# Converter.net
KiCad netlist of a schematic drawn in Altium Designer
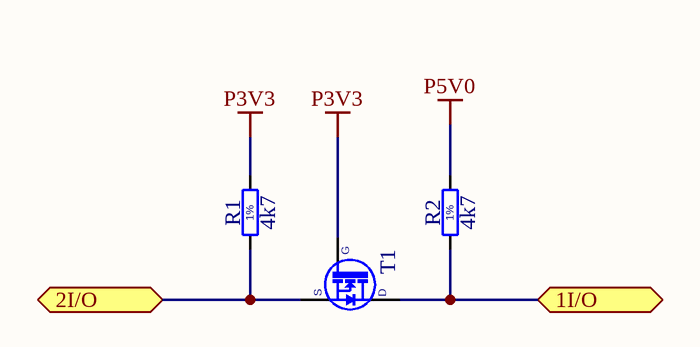
[diagram p0: Converter.SchDoc]

(export (version "E")
  (design (tool "Eeschema 10.0.6"))
  (components
    (comp (ref "R1")
      (value "4k7")
      (footprint "RESC1608X50N")
      (description "Resistor - 1%")
      (fields
        (field (name "PART NUMBER") "R0805_4K7_1%_0.125W_100PPM")
        (field (name "POWER") "0.125W")
        (field (name "AUTHOR") "CERN DEM JLC")
      )
      (libsource (lib "Resistors") (part "Resistor - 1%"))
    )
    (comp (ref "R2")
      (value "4k7")
      (footprint "RESC1608X50N")
      (description "Resistor - 1%")
      (fields
        (field (name "PART NUMBER") "R0805_4K7_1%_0.125W_100PPM")
        (field (name "POWER") "0.125W")
        (field (name "AUTHOR") "CERN DEM JLC")
      )
      (libsource (lib "Resistors") (part "Resistor - 1%"))
    )
    (comp (ref "T1")
      (value "~")
      (footprint "SOT95P240X110-3N")
      (description "N-CHANNEL MOSFET WITH DIODE")
      (fields
        (field (name "PART NUMBER") "BSS138LT1G")
        (field (name "MANUFACTURER") "ON SEMICONDUCTOR")
        (field (name "AUTHOR") "CERN DEM JLC")
      )
      (libsource (lib "ICs And Semiconductors") (part "N-MOSFET-D 1G 2S 3D"))
    )
  )
  (nets
    (net (code "1") (name "/1I{slash}O") (class "Default")
      (node (ref "R2") (pin "1") (pinfunction "1_1") (pintype "passive"))
      (node (ref "T1") (pin "3") (pinfunction "D_3") (pintype "passive"))
    )
    (net (code "2") (name "/2I{slash}O") (class "Default")
      (node (ref "R1") (pin "1") (pinfunction "1_1") (pintype "passive"))
      (node (ref "T1") (pin "2") (pinfunction "S_2") (pintype "passive"))
    )
    (net (code "3") (name "P3V3") (class "Default")
      (node (ref "R1") (pin "2") (pinfunction "2_2") (pintype "passive"))
      (node (ref "T1") (pin "1") (pinfunction "G_1") (pintype "passive"))
    )
    (net (code "4") (name "P5V0") (class "Default")
      (node (ref "R2") (pin "2") (pinfunction "2_2") (pintype "passive"))
    )
  )
)
